# STM32H755_Breakout_Schematic.net
KiCad netlist of a schematic drawn in Altium Designer
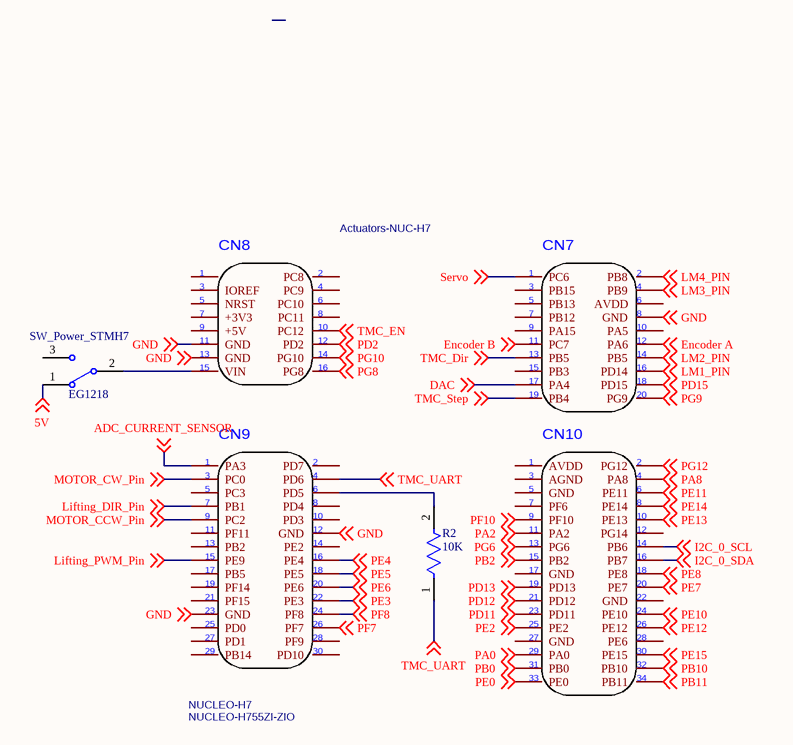
[diagram p0: STM32H755_Breakout_Schematic.SchDoc]

(export (version "E")
  (design (tool "Eeschema 10.0.6"))
  (components
    (comp (ref "Actuators-NUC-H7")
      (value "NUCLEO-H755ZI-ZIO")
      (footprint "NUCLEO-H7")
      (fields (field (name "CONTRIBUTOR") "zutawin"))
      (libsource (lib "Nucleo_H7") (part "NUCLEO-H755ZI-ZIO"))
    )
    (comp (ref "R2")
      (value "10K")
      (footprint "FP-MFR-12-MFG")
      (description "RES MF 1/6W 1% AXIAL")
      (fields (field (name "TOLERANCE") "1%"))
      (libsource (lib "Altium Content Vault") (part "1029c3af85768c4190bb7ad29bc67b5"))
    )
    (comp (ref "SW_Power_STMH7")
      (value "EG1218")
      (footprint "ESWI-EG1218_V")
      (description "Slide Switch, 500 V, -20 to 70 degC, 3-Pin THD, RoHS")
      (libsource (lib "Altium Content Vault") (part "SW-SPDT-3_B"))
    )
  )
  (nets
    (net (code "1") (name "5V") (class "Default")
      (node (ref "SW_Power_STMH7") (pin "1") (pinfunction "1_1") (pintype "passive"))
    )
    (net (code "2") (name "ADC_CURRENT_SENSOR") (class "Default")
      (node (ref "Actuators-NUC-H7") (pin "161") (pinfunction "PA3_161") (pintype "passive"))
    )
    (net (code "3") (name "DAC") (class "Default")
      (node (ref "Actuators-NUC-H7") (pin "207") (pinfunction "PA4_207") (pintype "passive"))
    )
    (net (code "4") (name "Encoder A") (class "Default")
      (node (ref "Actuators-NUC-H7") (pin "202") (pinfunction "PA6_202") (pintype "passive"))
    )
    (net (code "5") (name "Encoder B") (class "Default")
      (node (ref "Actuators-NUC-H7") (pin "201") (pinfunction "PC7_201") (pintype "passive"))
    )
    (net (code "6") (name "GND") (class "Default")
      (node (ref "Actuators-NUC-H7") (pin "155") (pinfunction "GND_155") (pintype "passive"))
      (node (ref "Actuators-NUC-H7") (pin "157") (pinfunction "GND_157") (pintype "passive"))
      (node (ref "Actuators-NUC-H7") (pin "172") (pinfunction "GND_172") (pintype "passive"))
      (node (ref "Actuators-NUC-H7") (pin "183") (pinfunction "GND_183") (pintype "passive"))
      (node (ref "Actuators-NUC-H7") (pin "198") (pinfunction "GND_198") (pintype "passive"))
    )
    (net (code "7") (name "I2C_0_SCL") (class "Default")
      (node (ref "Actuators-NUC-H7") (pin "224") (pinfunction "PB6_224") (pintype "passive"))
    )
    (net (code "8") (name "I2C_0_SDA") (class "Default")
      (node (ref "Actuators-NUC-H7") (pin "226") (pinfunction "PB7_226") (pintype "passive"))
    )
    (net (code "9") (name "LM1_PIN") (class "Default")
      (node (ref "Actuators-NUC-H7") (pin "206") (pinfunction "PD14_206") (pintype "passive"))
    )
    (net (code "10") (name "LM2_PIN") (class "Default")
      (node (ref "Actuators-NUC-H7") (pin "204") (pinfunction "PB5_204") (pintype "passive"))
    )
    (net (code "11") (name "LM3_PIN") (class "Default")
      (node (ref "Actuators-NUC-H7") (pin "194") (pinfunction "PB9_194") (pintype "passive"))
    )
    (net (code "12") (name "LM4_PIN") (class "Default")
      (node (ref "Actuators-NUC-H7") (pin "192") (pinfunction "PB8_192") (pintype "passive"))
    )
    (net (code "13") (name "Lifting_DIR_Pin") (class "Default")
      (node (ref "Actuators-NUC-H7") (pin "167") (pinfunction "PB1_167") (pintype "passive"))
    )
    (net (code "14") (name "Lifting_PWM_Pin") (class "Default")
      (node (ref "Actuators-NUC-H7") (pin "175") (pinfunction "PE9_175") (pintype "passive"))
    )
    (net (code "15") (name "MOTOR_CCW_Pin") (class "Default")
      (node (ref "Actuators-NUC-H7") (pin "169") (pinfunction "PC2_169") (pintype "passive"))
    )
    (net (code "16") (name "MOTOR_CW_Pin") (class "Default")
      (node (ref "Actuators-NUC-H7") (pin "163") (pinfunction "PC0_163") (pintype "passive"))
    )
    (net (code "17") (name "Net-(Actuators-NUC-H7-PD5)") (class "Default")
      (node (ref "Actuators-NUC-H7") (pin "166") (pinfunction "PD5_166") (pintype "passive"))
      (node (ref "R2") (pin "2") (pinfunction "2_2") (pintype "passive"))
    )
    (net (code "18") (name "Net-(Actuators-NUC-H7-VIN)") (class "Default")
      (node (ref "Actuators-NUC-H7") (pin "159") (pinfunction "VIN_159") (pintype "passive"))
      (node (ref "SW_Power_STMH7") (pin "2") (pinfunction "COM_2") (pintype "passive"))
    )
    (net (code "19") (name "PA0") (class "Default")
      (node (ref "Actuators-NUC-H7") (pin "239") (pinfunction "PA0_239") (pintype "passive"))
    )
    (net (code "20") (name "PA2") (class "Default")
      (node (ref "Actuators-NUC-H7") (pin "221") (pinfunction "PA2_221") (pintype "passive"))
    )
    (net (code "21") (name "PA8") (class "Default")
      (node (ref "Actuators-NUC-H7") (pin "214") (pinfunction "PA8_214") (pintype "passive"))
    )
    (net (code "22") (name "PB0") (class "Default")
      (node (ref "Actuators-NUC-H7") (pin "241") (pinfunction "PB0_241") (pintype "passive"))
    )
    (net (code "23") (name "PB2") (class "Default")
      (node (ref "Actuators-NUC-H7") (pin "225") (pinfunction "PB2_225") (pintype "passive"))
    )
    (net (code "24") (name "PB10") (class "Default")
      (node (ref "Actuators-NUC-H7") (pin "242") (pinfunction "PB10_242") (pintype "passive"))
    )
    (net (code "25") (name "PB11") (class "Default")
      (node (ref "Actuators-NUC-H7") (pin "244") (pinfunction "PB11_244") (pintype "passive"))
    )
    (net (code "26") (name "PD2") (class "Default")
      (node (ref "Actuators-NUC-H7") (pin "156") (pinfunction "PD2_156") (pintype "passive"))
    )
    (net (code "27") (name "PD11") (class "Default")
      (node (ref "Actuators-NUC-H7") (pin "233") (pinfunction "PD11_233") (pintype "passive"))
    )
    (net (code "28") (name "PD12") (class "Default")
      (node (ref "Actuators-NUC-H7") (pin "231") (pinfunction "PD12_231") (pintype "passive"))
    )
    (net (code "29") (name "PD13") (class "Default")
      (node (ref "Actuators-NUC-H7") (pin "229") (pinfunction "PD13_229") (pintype "passive"))
    )
    (net (code "30") (name "PD15") (class "Default")
      (node (ref "Actuators-NUC-H7") (pin "208") (pinfunction "PD15_208") (pintype "passive"))
    )
    (net (code "31") (name "PE0") (class "Default")
      (node (ref "Actuators-NUC-H7") (pin "243") (pinfunction "PE0_243") (pintype "passive"))
    )
    (net (code "32") (name "PE2") (class "Default")
      (node (ref "Actuators-NUC-H7") (pin "235") (pinfunction "PE2_235") (pintype "passive"))
    )
    (net (code "33") (name "PE3") (class "Default")
      (node (ref "Actuators-NUC-H7") (pin "182") (pinfunction "PE3_182") (pintype "passive"))
    )
    (net (code "34") (name "PE4") (class "Default")
      (node (ref "Actuators-NUC-H7") (pin "176") (pinfunction "PE4_176") (pintype "passive"))
    )
    (net (code "35") (name "PE5") (class "Default")
      (node (ref "Actuators-NUC-H7") (pin "178") (pinfunction "PE5_178") (pintype "passive"))
    )
    (net (code "36") (name "PE6") (class "Default")
      (node (ref "Actuators-NUC-H7") (pin "180") (pinfunction "PE6_180") (pintype "passive"))
    )
    (net (code "37") (name "PE7") (class "Default")
      (node (ref "Actuators-NUC-H7") (pin "230") (pinfunction "PE7_230") (pintype "passive"))
    )
    (net (code "38") (name "PE8") (class "Default")
      (node (ref "Actuators-NUC-H7") (pin "228") (pinfunction "PE8_228") (pintype "passive"))
    )
    (net (code "39") (name "PE10") (class "Default")
      (node (ref "Actuators-NUC-H7") (pin "234") (pinfunction "PE10_234") (pintype "passive"))
    )
    (net (code "40") (name "PE11") (class "Default")
      (node (ref "Actuators-NUC-H7") (pin "216") (pinfunction "PE11_216") (pintype "passive"))
    )
    (net (code "41") (name "PE12") (class "Default")
      (node (ref "Actuators-NUC-H7") (pin "236") (pinfunction "PE12_236") (pintype "passive"))
    )
    (net (code "42") (name "PE13") (class "Default")
      (node (ref "Actuators-NUC-H7") (pin "220") (pinfunction "PE13_220") (pintype "passive"))
    )
    (net (code "43") (name "PE14") (class "Default")
      (node (ref "Actuators-NUC-H7") (pin "218") (pinfunction "PE14_218") (pintype "passive"))
    )
    (net (code "44") (name "PE15") (class "Default")
      (node (ref "Actuators-NUC-H7") (pin "240") (pinfunction "PE15_240") (pintype "passive"))
    )
    (net (code "45") (name "PF7") (class "Default")
      (node (ref "Actuators-NUC-H7") (pin "186") (pinfunction "PF7_186") (pintype "passive"))
    )
    (net (code "46") (name "PF8") (class "Default")
      (node (ref "Actuators-NUC-H7") (pin "184") (pinfunction "PF8_184") (pintype "passive"))
    )
    (net (code "47") (name "PF10") (class "Default")
      (node (ref "Actuators-NUC-H7") (pin "219") (pinfunction "PF10_219") (pintype "passive"))
    )
    (net (code "48") (name "PG6") (class "Default")
      (node (ref "Actuators-NUC-H7") (pin "223") (pinfunction "PG6_223") (pintype "passive"))
    )
    (net (code "49") (name "PG8") (class "Default")
      (node (ref "Actuators-NUC-H7") (pin "160") (pinfunction "PG8_160") (pintype "passive"))
    )
    (net (code "50") (name "PG9") (class "Default")
      (node (ref "Actuators-NUC-H7") (pin "210") (pinfunction "PG9_210") (pintype "passive"))
    )
    (net (code "51") (name "PG10") (class "Default")
      (node (ref "Actuators-NUC-H7") (pin "158") (pinfunction "PG10_158") (pintype "passive"))
    )
    (net (code "52") (name "PG12") (class "Default")
      (node (ref "Actuators-NUC-H7") (pin "212") (pinfunction "PG12_212") (pintype "passive"))
    )
    (net (code "53") (name "Servo") (class "Default")
      (node (ref "Actuators-NUC-H7") (pin "191") (pinfunction "PC6_191") (pintype "passive"))
    )
    (net (code "54") (name "TMC_Dir") (class "Default")
      (node (ref "Actuators-NUC-H7") (pin "203") (pinfunction "PB5_203") (pintype "passive"))
    )
    (net (code "55") (name "TMC_EN") (class "Default")
      (node (ref "Actuators-NUC-H7") (pin "154") (pinfunction "PC12_154") (pintype "passive"))
    )
    (net (code "56") (name "TMC_Step") (class "Default")
      (node (ref "Actuators-NUC-H7") (pin "209") (pinfunction "PB4_209") (pintype "passive"))
    )
    (net (code "57") (name "TMC_UART") (class "Default")
      (node (ref "Actuators-NUC-H7") (pin "164") (pinfunction "PD6_164") (pintype "passive"))
      (node (ref "R2") (pin "1") (pinfunction "1_1") (pintype "passive"))
    )
    (net (code "58") (name "unconnected-(Actuators-NUC-H7-+3V3-Pad151)") (class "Default")
      (node (ref "Actuators-NUC-H7") (pin "151") (pinfunction "+3V3_151") (pintype "passive"))
    )
    (net (code "59") (name "unconnected-(Actuators-NUC-H7-+5V-Pad153)") (class "Default")
      (node (ref "Actuators-NUC-H7") (pin "153") (pinfunction "+5V_153") (pintype "passive"))
    )
    (net (code "60") (name "unconnected-(Actuators-NUC-H7-AGND-Pad213)") (class "Default")
      (node (ref "Actuators-NUC-H7") (pin "213") (pinfunction "AGND_213") (pintype "passive"))
    )
    (net (code "61") (name "unconnected-(Actuators-NUC-H7-AVDD-Pad196)") (class "Default")
      (node (ref "Actuators-NUC-H7") (pin "196") (pinfunction "AVDD_196") (pintype "passive"))
    )
    (net (code "62") (name "unconnected-(Actuators-NUC-H7-AVDD-Pad211)") (class "Default")
      (node (ref "Actuators-NUC-H7") (pin "211") (pinfunction "AVDD_211") (pintype "passive"))
    )
    (net (code "63") (name "unconnected-(Actuators-NUC-H7-GND-Pad215)") (class "Default")
      (node (ref "Actuators-NUC-H7") (pin "215") (pinfunction "GND_215") (pintype "passive"))
    )
    (net (code "64") (name "unconnected-(Actuators-NUC-H7-GND-Pad227)") (class "Default")
      (node (ref "Actuators-NUC-H7") (pin "227") (pinfunction "GND_227") (pintype "passive"))
    )
    (net (code "65") (name "unconnected-(Actuators-NUC-H7-GND-Pad232)") (class "Default")
      (node (ref "Actuators-NUC-H7") (pin "232") (pinfunction "GND_232") (pintype "passive"))
    )
    (net (code "66") (name "unconnected-(Actuators-NUC-H7-GND-Pad237)") (class "Default")
      (node (ref "Actuators-NUC-H7") (pin "237") (pinfunction "GND_237") (pintype "passive"))
    )
    (net (code "67") (name "unconnected-(Actuators-NUC-H7-IOREF-Pad147)") (class "Default")
      (node (ref "Actuators-NUC-H7") (pin "147") (pinfunction "IOREF_147") (pintype "passive"))
    )
    (net (code "68") (name "unconnected-(Actuators-NUC-H7-NRST-Pad149)") (class "Default")
      (node (ref "Actuators-NUC-H7") (pin "149") (pinfunction "NRST_149") (pintype "passive"))
    )
    (net (code "69") (name "unconnected-(Actuators-NUC-H7-PA5-Pad200)") (class "Default")
      (node (ref "Actuators-NUC-H7") (pin "200") (pinfunction "PA5_200") (pintype "passive"))
    )
    (net (code "70") (name "unconnected-(Actuators-NUC-H7-PA15-Pad199)") (class "Default")
      (node (ref "Actuators-NUC-H7") (pin "199") (pinfunction "PA15_199") (pintype "passive"))
    )
    (net (code "71") (name "unconnected-(Actuators-NUC-H7-PB2-Pad173)") (class "Default")
      (node (ref "Actuators-NUC-H7") (pin "173") (pinfunction "PB2_173") (pintype "passive"))
    )
    (net (code "72") (name "unconnected-(Actuators-NUC-H7-PB3-Pad205)") (class "Default")
      (node (ref "Actuators-NUC-H7") (pin "205") (pinfunction "PB3_205") (pintype "passive"))
    )
    (net (code "73") (name "unconnected-(Actuators-NUC-H7-PB5-Pad177)") (class "Default")
      (node (ref "Actuators-NUC-H7") (pin "177") (pinfunction "PB5_177") (pintype "passive"))
    )
    (net (code "74") (name "unconnected-(Actuators-NUC-H7-PB12-Pad197)") (class "Default")
      (node (ref "Actuators-NUC-H7") (pin "197") (pinfunction "PB12_197") (pintype "passive"))
    )
    (net (code "75") (name "unconnected-(Actuators-NUC-H7-PB13-Pad195)") (class "Default")
      (node (ref "Actuators-NUC-H7") (pin "195") (pinfunction "PB13_195") (pintype "passive"))
    )
    (net (code "76") (name "unconnected-(Actuators-NUC-H7-PB14-Pad189)") (class "Default")
      (node (ref "Actuators-NUC-H7") (pin "189") (pinfunction "PB14_189") (pintype "passive"))
    )
    (net (code "77") (name "unconnected-(Actuators-NUC-H7-PB15-Pad193)") (class "Default")
      (node (ref "Actuators-NUC-H7") (pin "193") (pinfunction "PB15_193") (pintype "passive"))
    )
    (net (code "78") (name "unconnected-(Actuators-NUC-H7-PC3-Pad165)") (class "Default")
      (node (ref "Actuators-NUC-H7") (pin "165") (pinfunction "PC3_165") (pintype "passive"))
    )
    (net (code "79") (name "unconnected-(Actuators-NUC-H7-PC8-Pad146)") (class "Default")
      (node (ref "Actuators-NUC-H7") (pin "146") (pinfunction "PC8_146") (pintype "passive"))
    )
    (net (code "80") (name "unconnected-(Actuators-NUC-H7-PC9-Pad148)") (class "Default")
      (node (ref "Actuators-NUC-H7") (pin "148") (pinfunction "PC9_148") (pintype "passive"))
    )
    (net (code "81") (name "unconnected-(Actuators-NUC-H7-PC10-Pad145)") (class "Default")
      (node (ref "Actuators-NUC-H7") (pin "145") (pinfunction "PC10_145") (pintype "passive"))
    )
    (net (code "82") (name "unconnected-(Actuators-NUC-H7-PC10-Pad150)") (class "Default")
      (node (ref "Actuators-NUC-H7") (pin "150") (pinfunction "PC10_150") (pintype "passive"))
    )
    (net (code "83") (name "unconnected-(Actuators-NUC-H7-PC11-Pad152)") (class "Default")
      (node (ref "Actuators-NUC-H7") (pin "152") (pinfunction "PC11_152") (pintype "passive"))
    )
    (net (code "84") (name "unconnected-(Actuators-NUC-H7-PD0-Pad185)") (class "Default")
      (node (ref "Actuators-NUC-H7") (pin "185") (pinfunction "PD0_185") (pintype "passive"))
    )
    (net (code "85") (name "unconnected-(Actuators-NUC-H7-PD1-Pad187)") (class "Default")
      (node (ref "Actuators-NUC-H7") (pin "187") (pinfunction "PD1_187") (pintype "passive"))
    )
    (net (code "86") (name "unconnected-(Actuators-NUC-H7-PD3-Pad170)") (class "Default")
      (node (ref "Actuators-NUC-H7") (pin "170") (pinfunction "PD3_170") (pintype "passive"))
    )
    (net (code "87") (name "unconnected-(Actuators-NUC-H7-PD4-Pad168)") (class "Default")
      (node (ref "Actuators-NUC-H7") (pin "168") (pinfunction "PD4_168") (pintype "passive"))
    )
    (net (code "88") (name "unconnected-(Actuators-NUC-H7-PD7-Pad162)") (class "Default")
      (node (ref "Actuators-NUC-H7") (pin "162") (pinfunction "PD7_162") (pintype "passive"))
    )
    (net (code "89") (name "unconnected-(Actuators-NUC-H7-PD10-Pad190)") (class "Default")
      (node (ref "Actuators-NUC-H7") (pin "190") (pinfunction "PD10_190") (pintype "passive"))
    )
    (net (code "90") (name "unconnected-(Actuators-NUC-H7-PE2-Pad174)") (class "Default")
      (node (ref "Actuators-NUC-H7") (pin "174") (pinfunction "PE2_174") (pintype "passive"))
    )
    (net (code "91") (name "unconnected-(Actuators-NUC-H7-PE6-Pad238)") (class "Default")
      (node (ref "Actuators-NUC-H7") (pin "238") (pinfunction "PE6_238") (pintype "passive"))
    )
    (net (code "92") (name "unconnected-(Actuators-NUC-H7-PF6-Pad217)") (class "Default")
      (node (ref "Actuators-NUC-H7") (pin "217") (pinfunction "PF6_217") (pintype "passive"))
    )
    (net (code "93") (name "unconnected-(Actuators-NUC-H7-PF9-Pad188)") (class "Default")
      (node (ref "Actuators-NUC-H7") (pin "188") (pinfunction "PF9_188") (pintype "passive"))
    )
    (net (code "94") (name "unconnected-(Actuators-NUC-H7-PF11-Pad171)") (class "Default")
      (node (ref "Actuators-NUC-H7") (pin "171") (pinfunction "PF11_171") (pintype "passive"))
    )
    (net (code "95") (name "unconnected-(Actuators-NUC-H7-PF14-Pad179)") (class "Default")
      (node (ref "Actuators-NUC-H7") (pin "179") (pinfunction "PF14_179") (pintype "passive"))
    )
    (net (code "96") (name "unconnected-(Actuators-NUC-H7-PF15-Pad181)") (class "Default")
      (node (ref "Actuators-NUC-H7") (pin "181") (pinfunction "PF15_181") (pintype "passive"))
    )
    (net (code "97") (name "unconnected-(Actuators-NUC-H7-PG14-Pad222)") (class "Default")
      (node (ref "Actuators-NUC-H7") (pin "222") (pinfunction "PG14_222") (pintype "passive"))
    )
    (net (code "98") (name "unconnected-(SW_Power_STMH7-Pad3)") (class "Default")
      (node (ref "SW_Power_STMH7") (pin "3") (pinfunction "3_3") (pintype "passive"))
    )
  )
)
